# placa1.net
KiCad netlist of a schematic drawn in Altium Designer
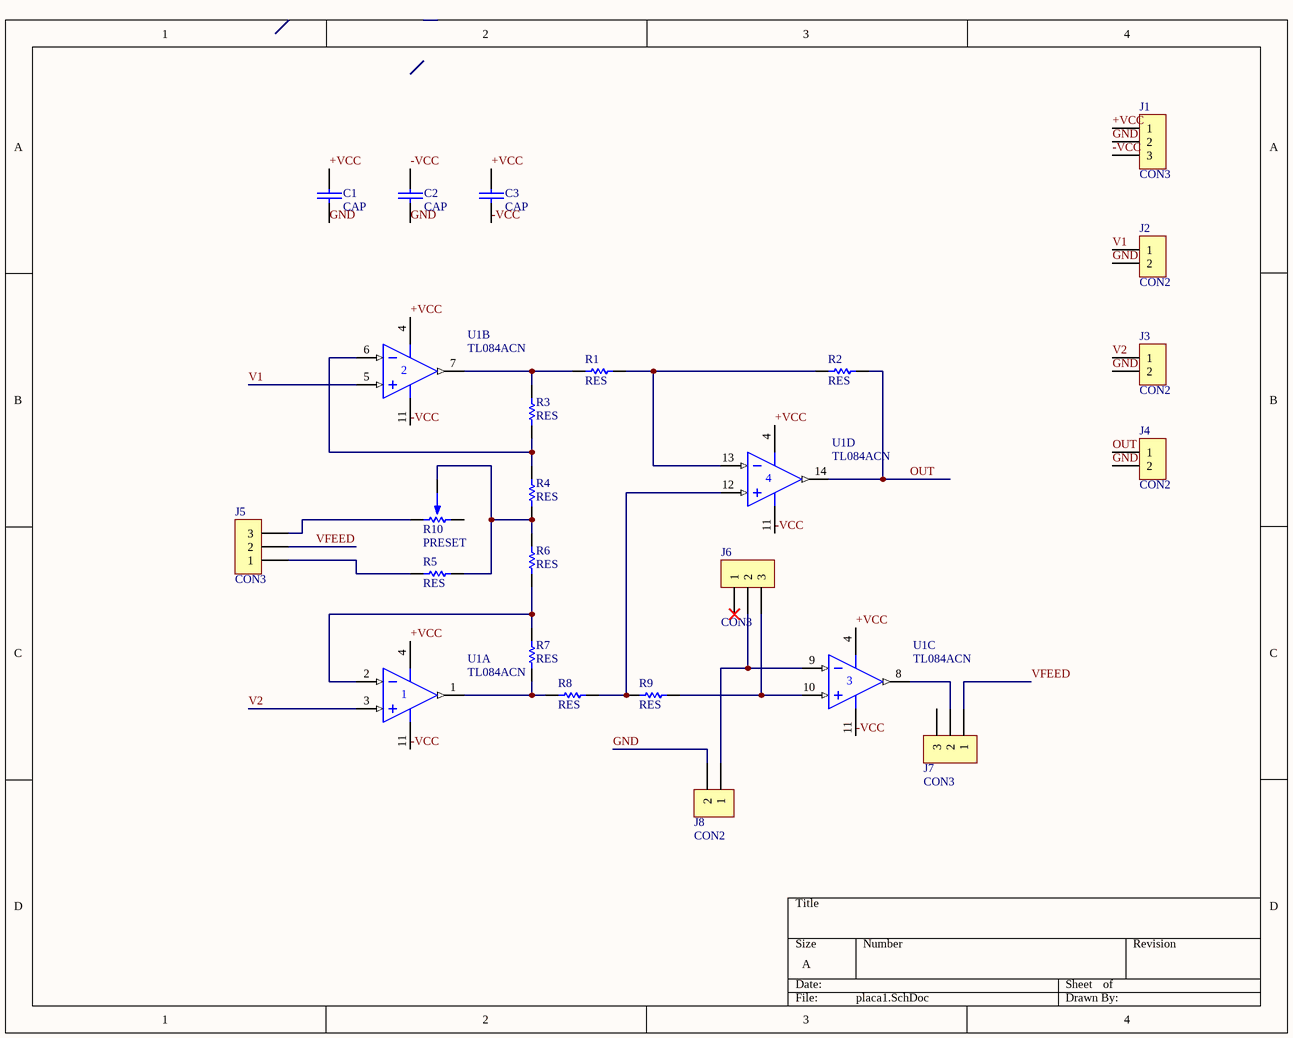
[diagram p0: placa1.SchDoc]

(export (version "E")
  (design (tool "Eeschema 10.0.6"))
  (components
    (comp (ref "C1") (value "CAP") (footprint "CAP200") (libsource (lib "LIBEBAL") (part "CAP")))
    (comp (ref "C2") (value "CAP") (footprint "CAP200") (libsource (lib "LIBEBAL") (part "CAP")))
    (comp (ref "C3") (value "CAP") (footprint "CAP200") (libsource (lib "LIBEBAL") (part "CAP")))
    (comp (ref "J1") (value "CON3") (footprint "SIP3") (libsource (lib "") (part "CON3_1")))
    (comp (ref "J2") (value "CON2") (footprint "SIP2") (libsource (lib "LIBEBAL") (part "CON2")))
    (comp (ref "J3") (value "CON2") (footprint "SIP2") (libsource (lib "LIBEBAL") (part "CON2")))
    (comp (ref "J4") (value "CON2") (footprint "SIP2") (libsource (lib "LIBEBAL") (part "CON2")))
    (comp (ref "J5") (value "CON3") (footprint "SIP3") (libsource (lib "") (part "CON3_2")))
    (comp (ref "J6") (value "CON3") (footprint "SIP3") (libsource (lib "") (part "CON3_3")))
    (comp (ref "J7") (value "CON3") (footprint "SIP3") (libsource (lib "LIBEBAL") (part "CON3")))
    (comp (ref "J8") (value "CON2") (footprint "SIP2") (libsource (lib "") (part "CON2_1")))
    (comp (ref "R1") (value "RES") (footprint "0805") (libsource (lib "LIBEBAL") (part "RES")))
    (comp (ref "R2") (value "RES") (footprint "0805") (libsource (lib "LIBEBAL") (part "RES")))
    (comp (ref "R3") (value "RES") (footprint "0805") (libsource (lib "LIBEBAL") (part "RES")))
    (comp (ref "R4") (value "RES") (footprint "0805") (libsource (lib "LIBEBAL") (part "RES")))
    (comp (ref "R5") (value "RES") (footprint "0805") (libsource (lib "LIBEBAL") (part "RES")))
    (comp (ref "R6") (value "RES") (footprint "0805") (libsource (lib "LIBEBAL") (part "RES")))
    (comp (ref "R7") (value "RES") (footprint "0805") (libsource (lib "LIBEBAL") (part "RES")))
    (comp (ref "R8") (value "RES") (footprint "0805") (libsource (lib "LIBEBAL") (part "RES")))
    (comp (ref "R9") (value "RES") (footprint "0805") (libsource (lib "LIBEBAL") (part "RES")))
    (comp (ref "R10") (value "PRESET") (footprint "PRESET V") (libsource (lib "LIBEBAL") (part "PRESET")))
    (comp (ref "U1")
      (value "TL084ACN")
      (footprint "646-06")
      (description "JFET-Input Operational Amplifier")
      (fields (field (name "PUBLISHER") "Altium Limited"))
      (libsource (lib "Motorola Amplifier Operational Amplifier") (part "TL084ACN"))
    )
  )
  (nets
    (net (code "1") (name "/+VCC") (class "Default")
      (node (ref "C1") (pin "1") (pinfunction "1_1") (pintype "passive"))
      (node (ref "C3") (pin "1") (pinfunction "1_1") (pintype "passive"))
      (node (ref "J1") (pin "1") (pinfunction "1_1") (pintype "passive"))
      (node (ref "U1") (pin "4") (pinfunction "V+_4") (pintype "power_in"))
    )
    (net (code "2") (name "/-VCC") (class "Default")
      (node (ref "C2") (pin "1") (pinfunction "1_1") (pintype "passive"))
      (node (ref "C3") (pin "2") (pinfunction "2_2") (pintype "passive"))
      (node (ref "J1") (pin "3") (pinfunction "3_3") (pintype "passive"))
      (node (ref "U1") (pin "11") (pinfunction "V-_11") (pintype "power_in"))
    )
    (net (code "3") (name "/GND") (class "Default")
      (node (ref "C1") (pin "2") (pinfunction "2_2") (pintype "passive"))
      (node (ref "C2") (pin "2") (pinfunction "2_2") (pintype "passive"))
      (node (ref "J1") (pin "2") (pinfunction "2_2") (pintype "passive"))
      (node (ref "J2") (pin "2") (pinfunction "2_2") (pintype "passive"))
      (node (ref "J3") (pin "2") (pinfunction "2_2") (pintype "passive"))
      (node (ref "J4") (pin "2") (pinfunction "2_2") (pintype "passive"))
      (node (ref "J8") (pin "2") (pinfunction "2_2") (pintype "passive"))
    )
    (net (code "4") (name "/OUT") (class "Default")
      (node (ref "J4") (pin "1") (pinfunction "1_1") (pintype "passive"))
      (node (ref "R2") (pin "2") (pinfunction "2_2") (pintype "passive"))
      (node (ref "U1") (pin "14") (pinfunction "OUT_14") (pintype "output"))
    )
    (net (code "5") (name "/V1") (class "Default")
      (node (ref "J2") (pin "1") (pinfunction "1_1") (pintype "passive"))
      (node (ref "U1") (pin "5") (pinfunction "IN+_5") (pintype "input"))
    )
    (net (code "6") (name "/V2") (class "Default")
      (node (ref "J3") (pin "1") (pinfunction "1_1") (pintype "passive"))
      (node (ref "U1") (pin "3") (pinfunction "IN+_3") (pintype "input"))
    )
    (net (code "7") (name "/VFEED") (class "Default")
      (node (ref "J5") (pin "2") (pinfunction "2_2") (pintype "passive"))
      (node (ref "J7") (pin "1") (pinfunction "1_1") (pintype "passive"))
    )
    (net (code "8") (name "Net-(J5-Pad1)") (class "Default")
      (node (ref "J5") (pin "1") (pinfunction "1_1") (pintype "passive"))
      (node (ref "R5") (pin "1") (pinfunction "1_1") (pintype "passive"))
    )
    (net (code "9") (name "Net-(J5-Pad3)") (class "Default")
      (node (ref "J5") (pin "3") (pinfunction "3_3") (pintype "passive"))
      (node (ref "R10") (pin "1") (pinfunction "1_1") (pintype "passive"))
    )
    (net (code "10") (name "Net-(R10-Pad2)") (class "Default")
      (node (ref "R10") (pin "2") (pinfunction "2_2") (pintype "passive"))
      (node (ref "R4") (pin "1") (pinfunction "1_1") (pintype "passive"))
      (node (ref "R5") (pin "2") (pinfunction "2_2") (pintype "passive"))
      (node (ref "R6") (pin "2") (pinfunction "2_2") (pintype "passive"))
    )
    (net (code "11") (name "Net-(U1A-IN-)") (class "Default")
      (node (ref "R6") (pin "1") (pinfunction "1_1") (pintype "passive"))
      (node (ref "R7") (pin "2") (pinfunction "2_2") (pintype "passive"))
      (node (ref "U1") (pin "2") (pinfunction "IN-_2") (pintype "input"))
    )
    (net (code "12") (name "Net-(U1A-OUT)") (class "Default")
      (node (ref "R7") (pin "1") (pinfunction "1_1") (pintype "passive"))
      (node (ref "R8") (pin "1") (pinfunction "1_1") (pintype "passive"))
      (node (ref "U1") (pin "1") (pinfunction "OUT_1") (pintype "output"))
    )
    (net (code "13") (name "Net-(U1B-IN-)") (class "Default")
      (node (ref "R3") (pin "1") (pinfunction "1_1") (pintype "passive"))
      (node (ref "R4") (pin "2") (pinfunction "2_2") (pintype "passive"))
      (node (ref "U1") (pin "6") (pinfunction "IN-_6") (pintype "input"))
    )
    (net (code "14") (name "Net-(U1B-OUT)") (class "Default")
      (node (ref "R1") (pin "1") (pinfunction "1_1") (pintype "passive"))
      (node (ref "R3") (pin "2") (pinfunction "2_2") (pintype "passive"))
      (node (ref "U1") (pin "7") (pinfunction "OUT_7") (pintype "output"))
    )
    (net (code "15") (name "Net-(U1C-IN+)") (class "Default")
      (node (ref "J6") (pin "3") (pinfunction "3_3") (pintype "passive"))
      (node (ref "R9") (pin "2") (pinfunction "2_2") (pintype "passive"))
      (node (ref "U1") (pin "10") (pinfunction "IN+_10") (pintype "input"))
    )
    (net (code "16") (name "Net-(U1C-IN-)") (class "Default")
      (node (ref "J6") (pin "2") (pinfunction "2_2") (pintype "passive"))
      (node (ref "J8") (pin "1") (pinfunction "1_1") (pintype "passive"))
      (node (ref "U1") (pin "9") (pinfunction "IN-_9") (pintype "input"))
    )
    (net (code "17") (name "Net-(U1C-OUT)") (class "Default")
      (node (ref "J7") (pin "2") (pinfunction "2_2") (pintype "passive"))
      (node (ref "U1") (pin "8") (pinfunction "OUT_8") (pintype "output"))
    )
    (net (code "18") (name "Net-(U1D-IN+)") (class "Default")
      (node (ref "R8") (pin "2") (pinfunction "2_2") (pintype "passive"))
      (node (ref "R9") (pin "1") (pinfunction "1_1") (pintype "passive"))
      (node (ref "U1") (pin "12") (pinfunction "IN+_12") (pintype "input"))
    )
    (net (code "19") (name "Net-(U1D-IN-)") (class "Default")
      (node (ref "R1") (pin "2") (pinfunction "2_2") (pintype "passive"))
      (node (ref "R2") (pin "1") (pinfunction "1_1") (pintype "passive"))
      (node (ref "U1") (pin "13") (pinfunction "IN-_13") (pintype "input"))
    )
    (net (code "20") (name "unconnected-(J6-Pad1)") (class "Default")
      (node (ref "J6") (pin "1") (pinfunction "1_1") (pintype "passive+no_connect"))
    )
    (net (code "21") (name "unconnected-(J7-Pad3)") (class "Default")
      (node (ref "J7") (pin "3") (pinfunction "3_3") (pintype "passive"))
    )
    (net (code "22") (name "unconnected-(R10-Pad3)") (class "Default")
      (node (ref "R10") (pin "3") (pinfunction "3_3") (pintype "passive"))
    )
  )
)
